# AmpCKT.net
KiCad netlist of a schematic drawn in Altium Designer
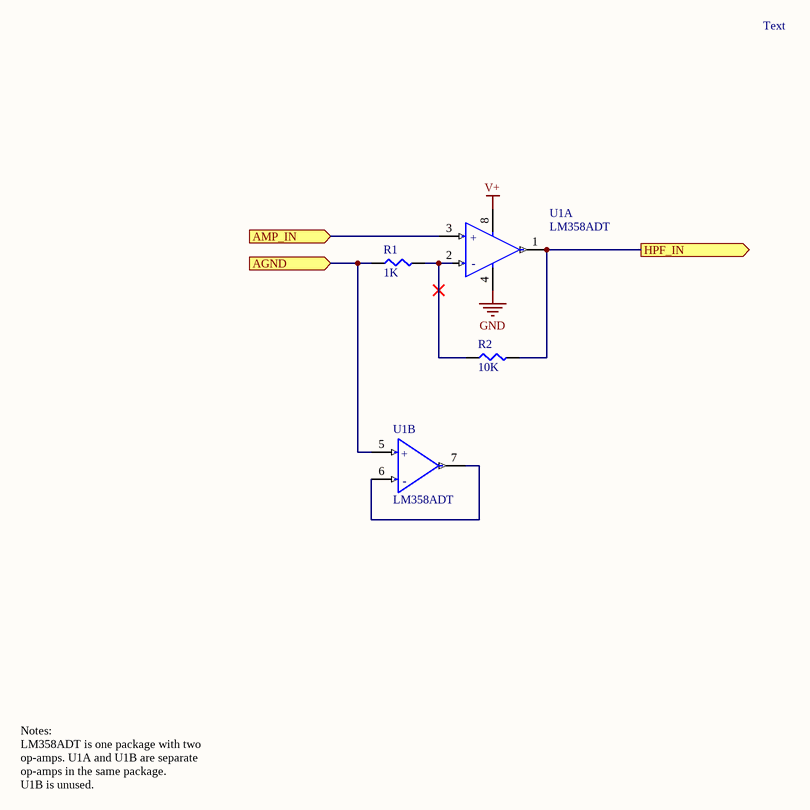
[diagram p0: AmpCKT.SchDoc]

(export (version "E")
  (design (tool "Eeschema 10.0.6"))
  (components
    (comp (ref "R1")
      (value "1K")
      (footprint "SMD-0805-RES")
      (fields
        (field (name "MANUFACTURER") "Stackpole Electronics Inc")
        (field (name "MANUFACTURER PART NUMBER") "RMCF0805FT1K00")
      )
      (libsource (lib "Panasonic_resistor_0805") (part "ERJ-6ENF1001V"))
    )
    (comp (ref "R2")
      (value "10K")
      (footprint "SMD-0805-RES")
      (fields
        (field (name "MANUFACTURER") "Stackpole Electronics Inc")
        (field (name "MANUFACTURER PART NUMBER") "RMCF0805JG10K0")
      )
      (libsource (lib "Panasonic_resistor_0805") (part "ERJ-6ENF1002V"))
    )
    (comp (ref "U1")
      (value "LM358ADT")
      (footprint "FP-SO8-IPC_C")
      (fields
        (field (name "MANUFACTURER PART NUMBER") "LM358WDT")
        (field (name "MANUFACTURER") "STMicroelectronics")
      )
      (libsource (lib "Altium Content Vault") (part "9f386d5a0a155305257da89b0c2f71e"))
    )
  )
  (nets
    (net (code "1") (name "/AGND") (class "Default")
      (node (ref "R1") (pin "1") (pinfunction "1_1") (pintype "passive"))
      (node (ref "U1") (pin "5") (pinfunction "In2+_5") (pintype "tri_state"))
    )
    (net (code "2") (name "/AMP_IN") (class "Default")
      (node (ref "U1") (pin "3") (pinfunction "In1+_3") (pintype "input"))
    )
    (net (code "3") (name "/HPF_IN") (class "Default")
      (node (ref "R2") (pin "2") (pinfunction "2_2") (pintype "passive"))
      (node (ref "U1") (pin "1") (pinfunction "Out1_1") (pintype "output"))
    )
    (net (code "4") (name "GND") (class "Default")
      (node (ref "U1") (pin "4") (pinfunction "VCC-_4") (pintype "power_in"))
    )
    (net (code "5") (name "Net-(U1A-In1-)") (class "Default")
      (node (ref "R1") (pin "2") (pinfunction "2_2") (pintype "passive"))
      (node (ref "R2") (pin "1") (pinfunction "1_1") (pintype "passive"))
      (node (ref "U1") (pin "2") (pinfunction "In1-_2") (pintype "input"))
    )
    (net (code "6") (name "Net-(U1B-In2-)") (class "Default")
      (node (ref "U1") (pin "6") (pinfunction "In2-_6") (pintype "tri_state"))
      (node (ref "U1") (pin "7") (pinfunction "Out2_7") (pintype "passive"))
    )
    (net (code "7") (name "V+") (class "Default")
      (node (ref "U1") (pin "8") (pinfunction "VCC+_8") (pintype "power_in"))
    )
  )
)
